# Sheet1.net
KiCad netlist of a schematic drawn in Altium Designer
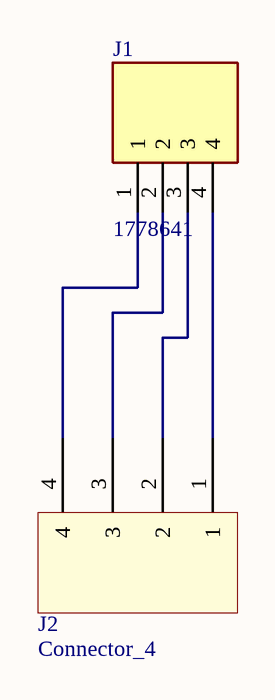
[diagram p0: Sheet1.SchDoc]

(export (version "E")
  (design (tool "Eeschema 10.0.6"))
  (components
    (comp (ref "J1")
      (value "1778641")
      (footprint "SHDRRA4W60P0X250_1X4_1170X750X510P")
      (fields (field (name "MOUSER PART NUMBER") "651-1778641"))
      (libsource (lib "PTSM") (part "1778641"))
    )
    (comp (ref "J2")
      (value "Connector_4")
      (footprint "PTSM 0,5/ 4-2,5-H THR WH R32")
      (libsource (lib "PTSM") (part "Connector_4"))
    )
  )
  (nets
    (net (code "1") (name "Net-(J1-Pad1)") (class "Default")
      (node (ref "J1") (pin "1") (pinfunction "1_1") (pintype "passive"))
      (node (ref "J2") (pin "4") (pinfunction "4_4") (pintype "passive"))
    )
    (net (code "2") (name "Net-(J1-Pad2)") (class "Default")
      (node (ref "J1") (pin "2") (pinfunction "2_2") (pintype "passive"))
      (node (ref "J2") (pin "3") (pinfunction "3_3") (pintype "passive"))
    )
    (net (code "3") (name "Net-(J1-Pad3)") (class "Default")
      (node (ref "J1") (pin "3") (pinfunction "3_3") (pintype "passive"))
      (node (ref "J2") (pin "2") (pinfunction "2_2") (pintype "passive"))
    )
    (net (code "4") (name "Net-(J1-Pad4)") (class "Default")
      (node (ref "J1") (pin "4") (pinfunction "4_4") (pintype "passive"))
      (node (ref "J2") (pin "1") (pinfunction "1_1") (pintype "passive"))
    )
  )
)
